# s-tuner_demo_board.net
KiCad netlist of a schematic drawn in EAGLE
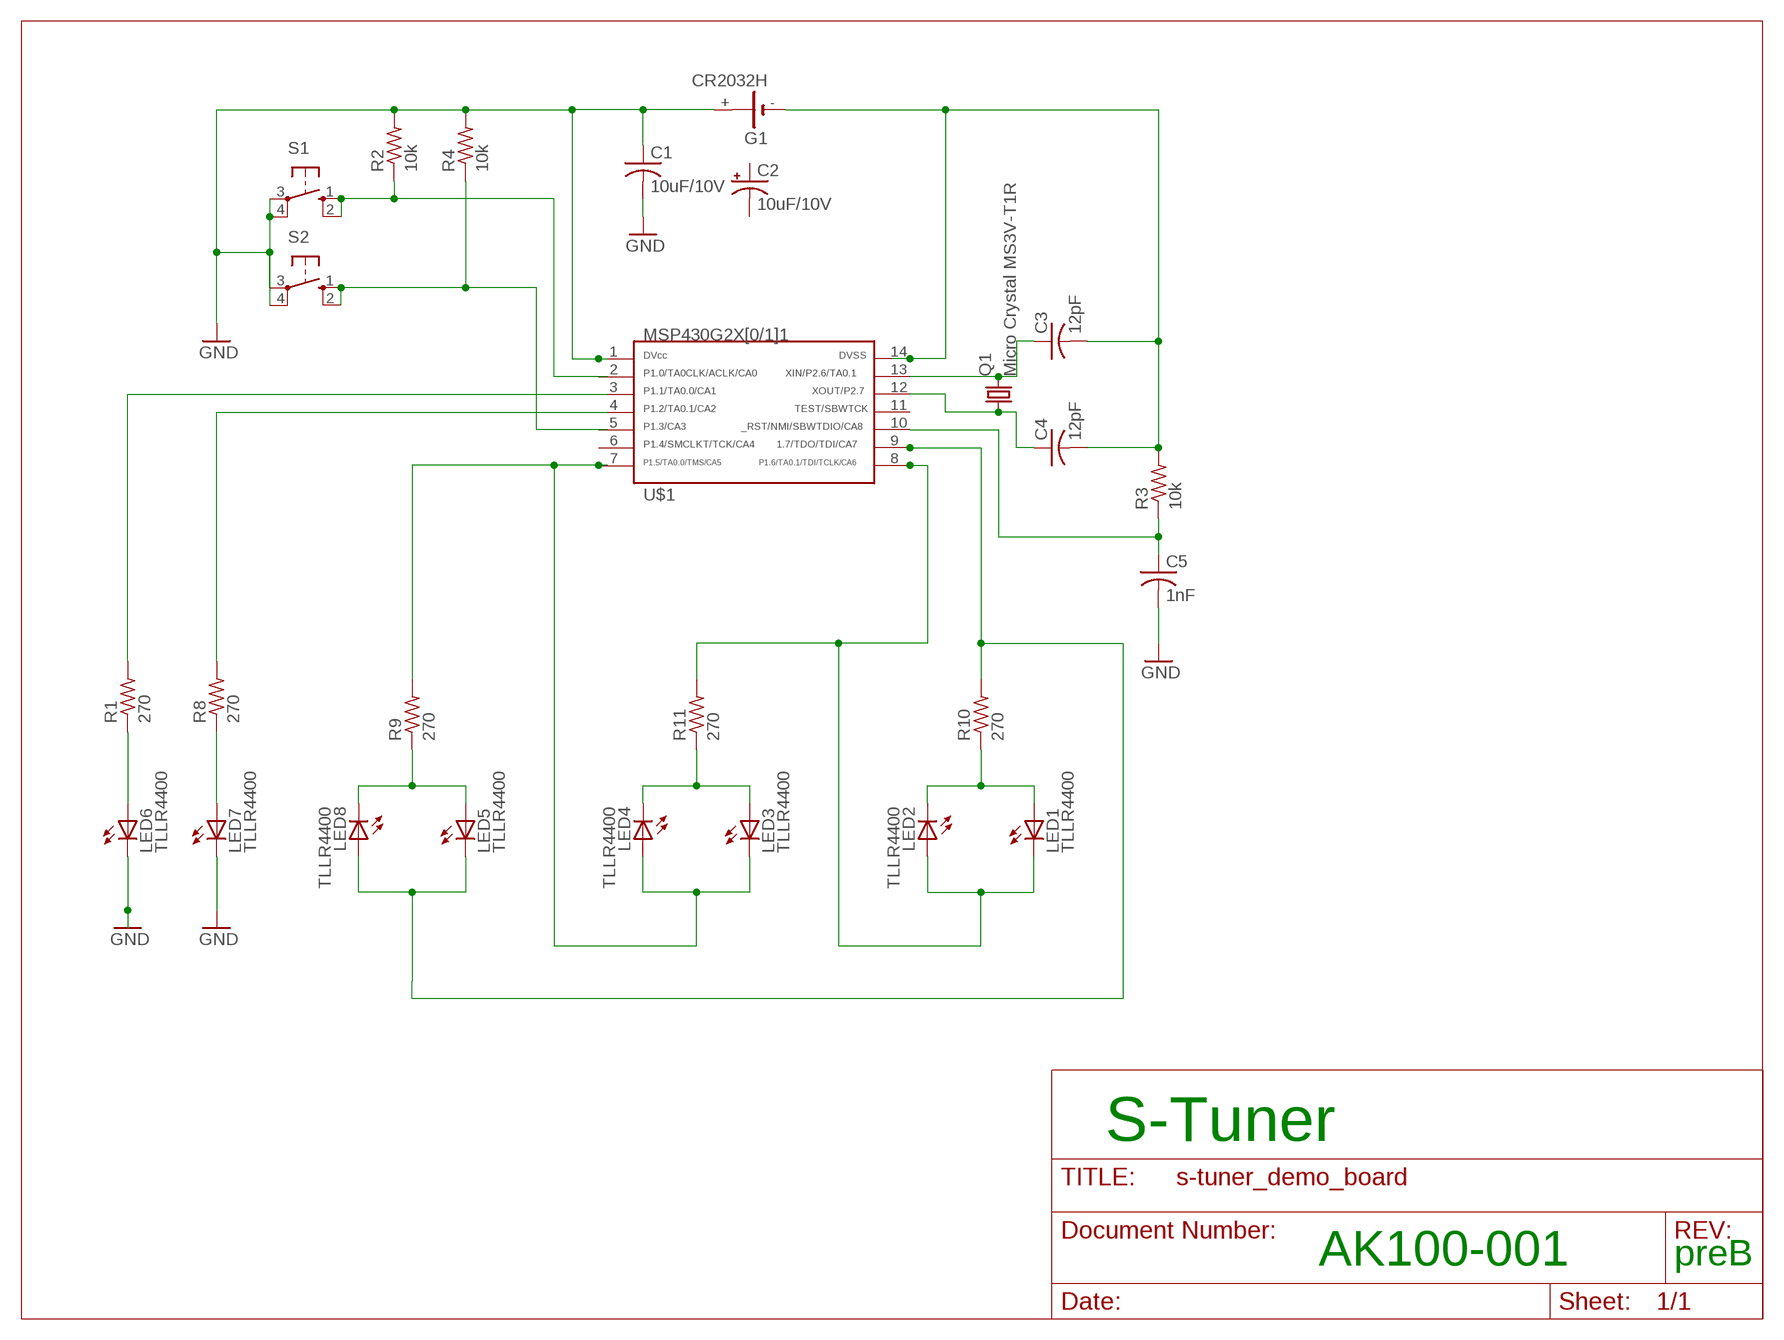
[diagram p0: schematic, sheet 1]

(export (version "E")
  (design (tool "Eeschema 10.0.6"))
  (components
    (comp (ref "C1")
      (value "10uF/10V")
      (footprint "eagle-import:C0805")
      (libsource (lib "eagle-import") (part "C-USC0805"))
    )
    (comp (ref "C2")
      (value "10uF/10V")
      (footprint "eagle-import:SMC_B")
      (libsource (lib "eagle-import") (part "CPOL-USSMCB"))
    )
    (comp (ref "C3")
      (value "12pF")
      (footprint "eagle-import:C0805")
      (libsource (lib "eagle-import") (part "resistor_C-USC0805"))
    )
    (comp (ref "C4")
      (value "12pF")
      (footprint "eagle-import:C0805")
      (libsource (lib "eagle-import") (part "resistor_C-USC0805"))
    )
    (comp (ref "C5")
      (value "1nF")
      (footprint "eagle-import:C0805")
      (libsource (lib "eagle-import") (part "resistor_C-USC0805"))
    )
    (comp (ref "G1")
      (value "CR2032H")
      (footprint "eagle-import:CR2032H")
      (libsource (lib "eagle-import") (part "CR2032H"))
    )
    (comp (ref "LED1")
      (value "TLLR4400")
      (footprint "eagle-import:LED3MM")
      (fields (field (name "MF") "VISHAY SEMICONDUCTOR"))
      (libsource (lib "eagle-import") (part "TLLR4400"))
    )
    (comp (ref "LED2")
      (value "TLLR4400")
      (footprint "eagle-import:LED3MM")
      (fields (field (name "MF") "VISHAY SEMICONDUCTOR"))
      (libsource (lib "eagle-import") (part "TLLR4400"))
    )
    (comp (ref "LED3")
      (value "TLLR4400")
      (footprint "eagle-import:LED3MM")
      (fields (field (name "MF") "VISHAY SEMICONDUCTOR"))
      (libsource (lib "eagle-import") (part "TLLR4400"))
    )
    (comp (ref "LED4")
      (value "TLLR4400")
      (footprint "eagle-import:LED3MM")
      (fields (field (name "MF") "VISHAY SEMICONDUCTOR"))
      (libsource (lib "eagle-import") (part "TLLR4400"))
    )
    (comp (ref "LED5")
      (value "TLLR4400")
      (footprint "eagle-import:LED3MM")
      (fields (field (name "MF") "VISHAY SEMICONDUCTOR"))
      (libsource (lib "eagle-import") (part "TLLR4400"))
    )
    (comp (ref "LED6")
      (value "TLLR4400")
      (footprint "eagle-import:LED3MM")
      (fields (field (name "MF") "VISHAY SEMICONDUCTOR"))
      (libsource (lib "eagle-import") (part "TLLR4400"))
    )
    (comp (ref "LED7")
      (value "TLLR4400")
      (footprint "eagle-import:LED3MM")
      (fields (field (name "MF") "VISHAY SEMICONDUCTOR"))
      (libsource (lib "eagle-import") (part "TLLR4400"))
    )
    (comp (ref "LED8")
      (value "TLLR4400")
      (footprint "eagle-import:LED3MM")
      (fields (field (name "MF") "VISHAY SEMICONDUCTOR"))
      (libsource (lib "eagle-import") (part "TLLR4400"))
    )
    (comp (ref "Q1")
      (value "Micro Crystal MS3V-T1R")
      (footprint "eagle-import:TC26H")
      (libsource (lib "eagle-import") (part "CRYSTALTC26H"))
    )
    (comp (ref "R1")
      (value "270")
      (footprint "eagle-import:R0805")
      (libsource (lib "eagle-import") (part "R-US_R0805"))
    )
    (comp (ref "R2")
      (value "10k")
      (footprint "eagle-import:R0805")
      (libsource (lib "eagle-import") (part "R-US_R0805"))
    )
    (comp (ref "R3")
      (value "10k")
      (footprint "eagle-import:R0805")
      (libsource (lib "eagle-import") (part "R-US_R0805"))
    )
    (comp (ref "R4")
      (value "10k")
      (footprint "eagle-import:R0805")
      (libsource (lib "eagle-import") (part "R-US_R0805"))
    )
    (comp (ref "R8")
      (value "270")
      (footprint "eagle-import:R0805")
      (libsource (lib "eagle-import") (part "R-US_R0805"))
    )
    (comp (ref "R9")
      (value "270")
      (footprint "eagle-import:R0805")
      (libsource (lib "eagle-import") (part "R-US_R0805"))
    )
    (comp (ref "R10")
      (value "270")
      (footprint "eagle-import:R0805")
      (libsource (lib "eagle-import") (part "R-US_R0805"))
    )
    (comp (ref "R11")
      (value "270")
      (footprint "eagle-import:R0805")
      (libsource (lib "eagle-import") (part "R-US_R0805"))
    )
    (comp (ref "S1")
      (value "10-XX")
      (footprint "eagle-import:B3F-10XX")
      (fields (field (name "MPN") "B3F-1000"))
      (libsource (lib "eagle-import") (part "10-XX"))
    )
    (comp (ref "S2")
      (value "10-XX")
      (footprint "eagle-import:B3F-10XX")
      (fields (field (name "MPN") "B3F-1000"))
      (libsource (lib "eagle-import") (part "10-XX"))
    )
    (comp (ref "U$1")
      (value "G2X[0/1]1---N14")
      (footprint "eagle-import:N14")
      (libsource (lib "eagle-import") (part "G2X[0/1]1---N14"))
    )
  )
  (nets
    (net (code "1") (name "GND") (class "Default")
      (node (ref "C1") (pin "1") (pinfunction "1_1") (pintype "passive"))
      (node (ref "C1") (pin "2") (pinfunction "2_2") (pintype "passive"))
      (node (ref "C5") (pin "2") (pinfunction "2_2") (pintype "passive"))
      (node (ref "G1") (pin "+") (pinfunction "+_+") (pintype "passive"))
      (node (ref "LED6") (pin "K") (pinfunction "C_K") (pintype "passive"))
      (node (ref "LED7") (pin "K") (pinfunction "C_K") (pintype "passive"))
      (node (ref "R2") (pin "2") (pinfunction "2_2") (pintype "passive"))
      (node (ref "R4") (pin "2") (pinfunction "2_2") (pintype "passive"))
      (node (ref "S1") (pin "3") (pinfunction "P_3") (pintype "passive"))
      (node (ref "S1") (pin "4") (pinfunction "P1_4") (pintype "passive"))
      (node (ref "S2") (pin "3") (pinfunction "P_3") (pintype "passive"))
      (node (ref "S2") (pin "4") (pinfunction "P1_4") (pintype "passive"))
      (node (ref "U$1") (pin "1") (pinfunction "1_1") (pintype "bidirectional"))
    )
    (net (code "2") (name "Net-(C3-Pad1)") (class "Default")
      (node (ref "C3") (pin "1") (pinfunction "1_1") (pintype "passive"))
      (node (ref "Q1") (pin "2") (pinfunction "2_2") (pintype "passive"))
      (node (ref "U$1") (pin "13") (pinfunction "13_13") (pintype "bidirectional"))
    )
    (net (code "3") (name "Net-(C3-Pad2)") (class "Default")
      (node (ref "C3") (pin "2") (pinfunction "2_2") (pintype "passive"))
      (node (ref "C4") (pin "2") (pinfunction "2_2") (pintype "passive"))
      (node (ref "G1") (pin "-") (pinfunction "-_-") (pintype "passive"))
      (node (ref "R3") (pin "2") (pinfunction "2_2") (pintype "passive"))
      (node (ref "U$1") (pin "14") (pinfunction "14_14") (pintype "bidirectional"))
    )
    (net (code "4") (name "Net-(C4-Pad1)") (class "Default")
      (node (ref "C4") (pin "1") (pinfunction "1_1") (pintype "passive"))
      (node (ref "Q1") (pin "1") (pinfunction "1_1") (pintype "passive"))
      (node (ref "U$1") (pin "12") (pinfunction "12_12") (pintype "bidirectional"))
    )
    (net (code "5") (name "Net-(C5-Pad1)") (class "Default")
      (node (ref "C5") (pin "1") (pinfunction "1_1") (pintype "passive"))
      (node (ref "R3") (pin "1") (pinfunction "1_1") (pintype "passive"))
      (node (ref "U$1") (pin "10") (pinfunction "10_10") (pintype "bidirectional"))
    )
    (net (code "6") (name "Net-(LED1-C)") (class "Default")
      (node (ref "LED1") (pin "K") (pinfunction "C_K") (pintype "passive"))
      (node (ref "LED2") (pin "A") (pinfunction "A_A") (pintype "passive"))
      (node (ref "R11") (pin "2") (pinfunction "2_2") (pintype "passive"))
      (node (ref "U$1") (pin "8") (pinfunction "8_8") (pintype "bidirectional"))
    )
    (net (code "7") (name "Net-(LED2-C)") (class "Default")
      (node (ref "LED1") (pin "A") (pinfunction "A_A") (pintype "passive"))
      (node (ref "LED2") (pin "K") (pinfunction "C_K") (pintype "passive"))
      (node (ref "R10") (pin "1") (pinfunction "1_1") (pintype "passive"))
    )
    (net (code "8") (name "Net-(LED3-C)") (class "Default")
      (node (ref "LED3") (pin "K") (pinfunction "C_K") (pintype "passive"))
      (node (ref "LED4") (pin "A") (pinfunction "A_A") (pintype "passive"))
      (node (ref "R9") (pin "2") (pinfunction "2_2") (pintype "passive"))
      (node (ref "U$1") (pin "7") (pinfunction "7_7") (pintype "bidirectional"))
    )
    (net (code "9") (name "Net-(LED4-C)") (class "Default")
      (node (ref "LED3") (pin "A") (pinfunction "A_A") (pintype "passive"))
      (node (ref "LED4") (pin "K") (pinfunction "C_K") (pintype "passive"))
      (node (ref "R11") (pin "1") (pinfunction "1_1") (pintype "passive"))
    )
    (net (code "10") (name "Net-(LED5-C)") (class "Default")
      (node (ref "LED5") (pin "K") (pinfunction "C_K") (pintype "passive"))
      (node (ref "LED8") (pin "A") (pinfunction "A_A") (pintype "passive"))
      (node (ref "R10") (pin "2") (pinfunction "2_2") (pintype "passive"))
      (node (ref "U$1") (pin "9") (pinfunction "9_9") (pintype "bidirectional"))
    )
    (net (code "11") (name "Net-(LED6-PadA)") (class "Default")
      (node (ref "LED6") (pin "A") (pinfunction "A_A") (pintype "passive"))
      (node (ref "R1") (pin "1") (pinfunction "1_1") (pintype "passive"))
    )
    (net (code "12") (name "Net-(LED7-PadA)") (class "Default")
      (node (ref "LED7") (pin "A") (pinfunction "A_A") (pintype "passive"))
      (node (ref "R8") (pin "1") (pinfunction "1_1") (pintype "passive"))
    )
    (net (code "13") (name "Net-(LED8-C)") (class "Default")
      (node (ref "LED5") (pin "A") (pinfunction "A_A") (pintype "passive"))
      (node (ref "LED8") (pin "K") (pinfunction "C_K") (pintype "passive"))
      (node (ref "R9") (pin "1") (pinfunction "1_1") (pintype "passive"))
    )
    (net (code "14") (name "Net-(S1-S)") (class "Default")
      (node (ref "R2") (pin "1") (pinfunction "1_1") (pintype "passive"))
      (node (ref "S1") (pin "1") (pinfunction "S_1") (pintype "passive"))
      (node (ref "S1") (pin "2") (pinfunction "S1_2") (pintype "passive"))
    )
    (net (code "15") (name "Net-(S2-S)") (class "Default")
      (node (ref "R4") (pin "1") (pinfunction "1_1") (pintype "passive"))
      (node (ref "S2") (pin "1") (pinfunction "S_1") (pintype "passive"))
      (node (ref "S2") (pin "2") (pinfunction "S1_2") (pintype "passive"))
    )
    (net (code "16") (name "unconnected-(C2-Pad+)") (class "Default")
      (node (ref "C2") (pin "+") (pinfunction "+_+") (pintype "passive"))
    )
    (net (code "17") (name "unconnected-(C2-Pad-)") (class "Default")
      (node (ref "C2") (pin "-") (pinfunction "-_-") (pintype "passive"))
    )
    (net (code "18") (name "unconnected-(G1-+-Pad+@1)") (class "Default")
      (node (ref "G1") (pin "+@1") (pinfunction "+_+@1") (pintype "passive"))
    )
    (net (code "19") (name "unconnected-(R1-Pad2)") (class "Default")
      (node (ref "R1") (pin "2") (pinfunction "2_2") (pintype "passive"))
    )
    (net (code "20") (name "unconnected-(R8-Pad2)") (class "Default")
      (node (ref "R8") (pin "2") (pinfunction "2_2") (pintype "passive"))
    )
    (net (code "21") (name "unconnected-(U$1-Pad2)") (class "Default")
      (node (ref "U$1") (pin "2") (pinfunction "2_2") (pintype "bidirectional"))
    )
    (net (code "22") (name "unconnected-(U$1-Pad3)") (class "Default")
      (node (ref "U$1") (pin "3") (pinfunction "3_3") (pintype "bidirectional"))
    )
    (net (code "23") (name "unconnected-(U$1-Pad4)") (class "Default")
      (node (ref "U$1") (pin "4") (pinfunction "4_4") (pintype "bidirectional"))
    )
    (net (code "24") (name "unconnected-(U$1-Pad5)") (class "Default")
      (node (ref "U$1") (pin "5") (pinfunction "5_5") (pintype "bidirectional"))
    )
    (net (code "25") (name "unconnected-(U$1-Pad6)") (class "Default")
      (node (ref "U$1") (pin "6") (pinfunction "6_6") (pintype "bidirectional"))
    )
    (net (code "26") (name "unconnected-(U$1-Pad11)") (class "Default")
      (node (ref "U$1") (pin "11") (pinfunction "11_11") (pintype "bidirectional"))
    )
  )
)
